# Lab2_Schematic.net
KiCad netlist of a schematic drawn in EAGLE
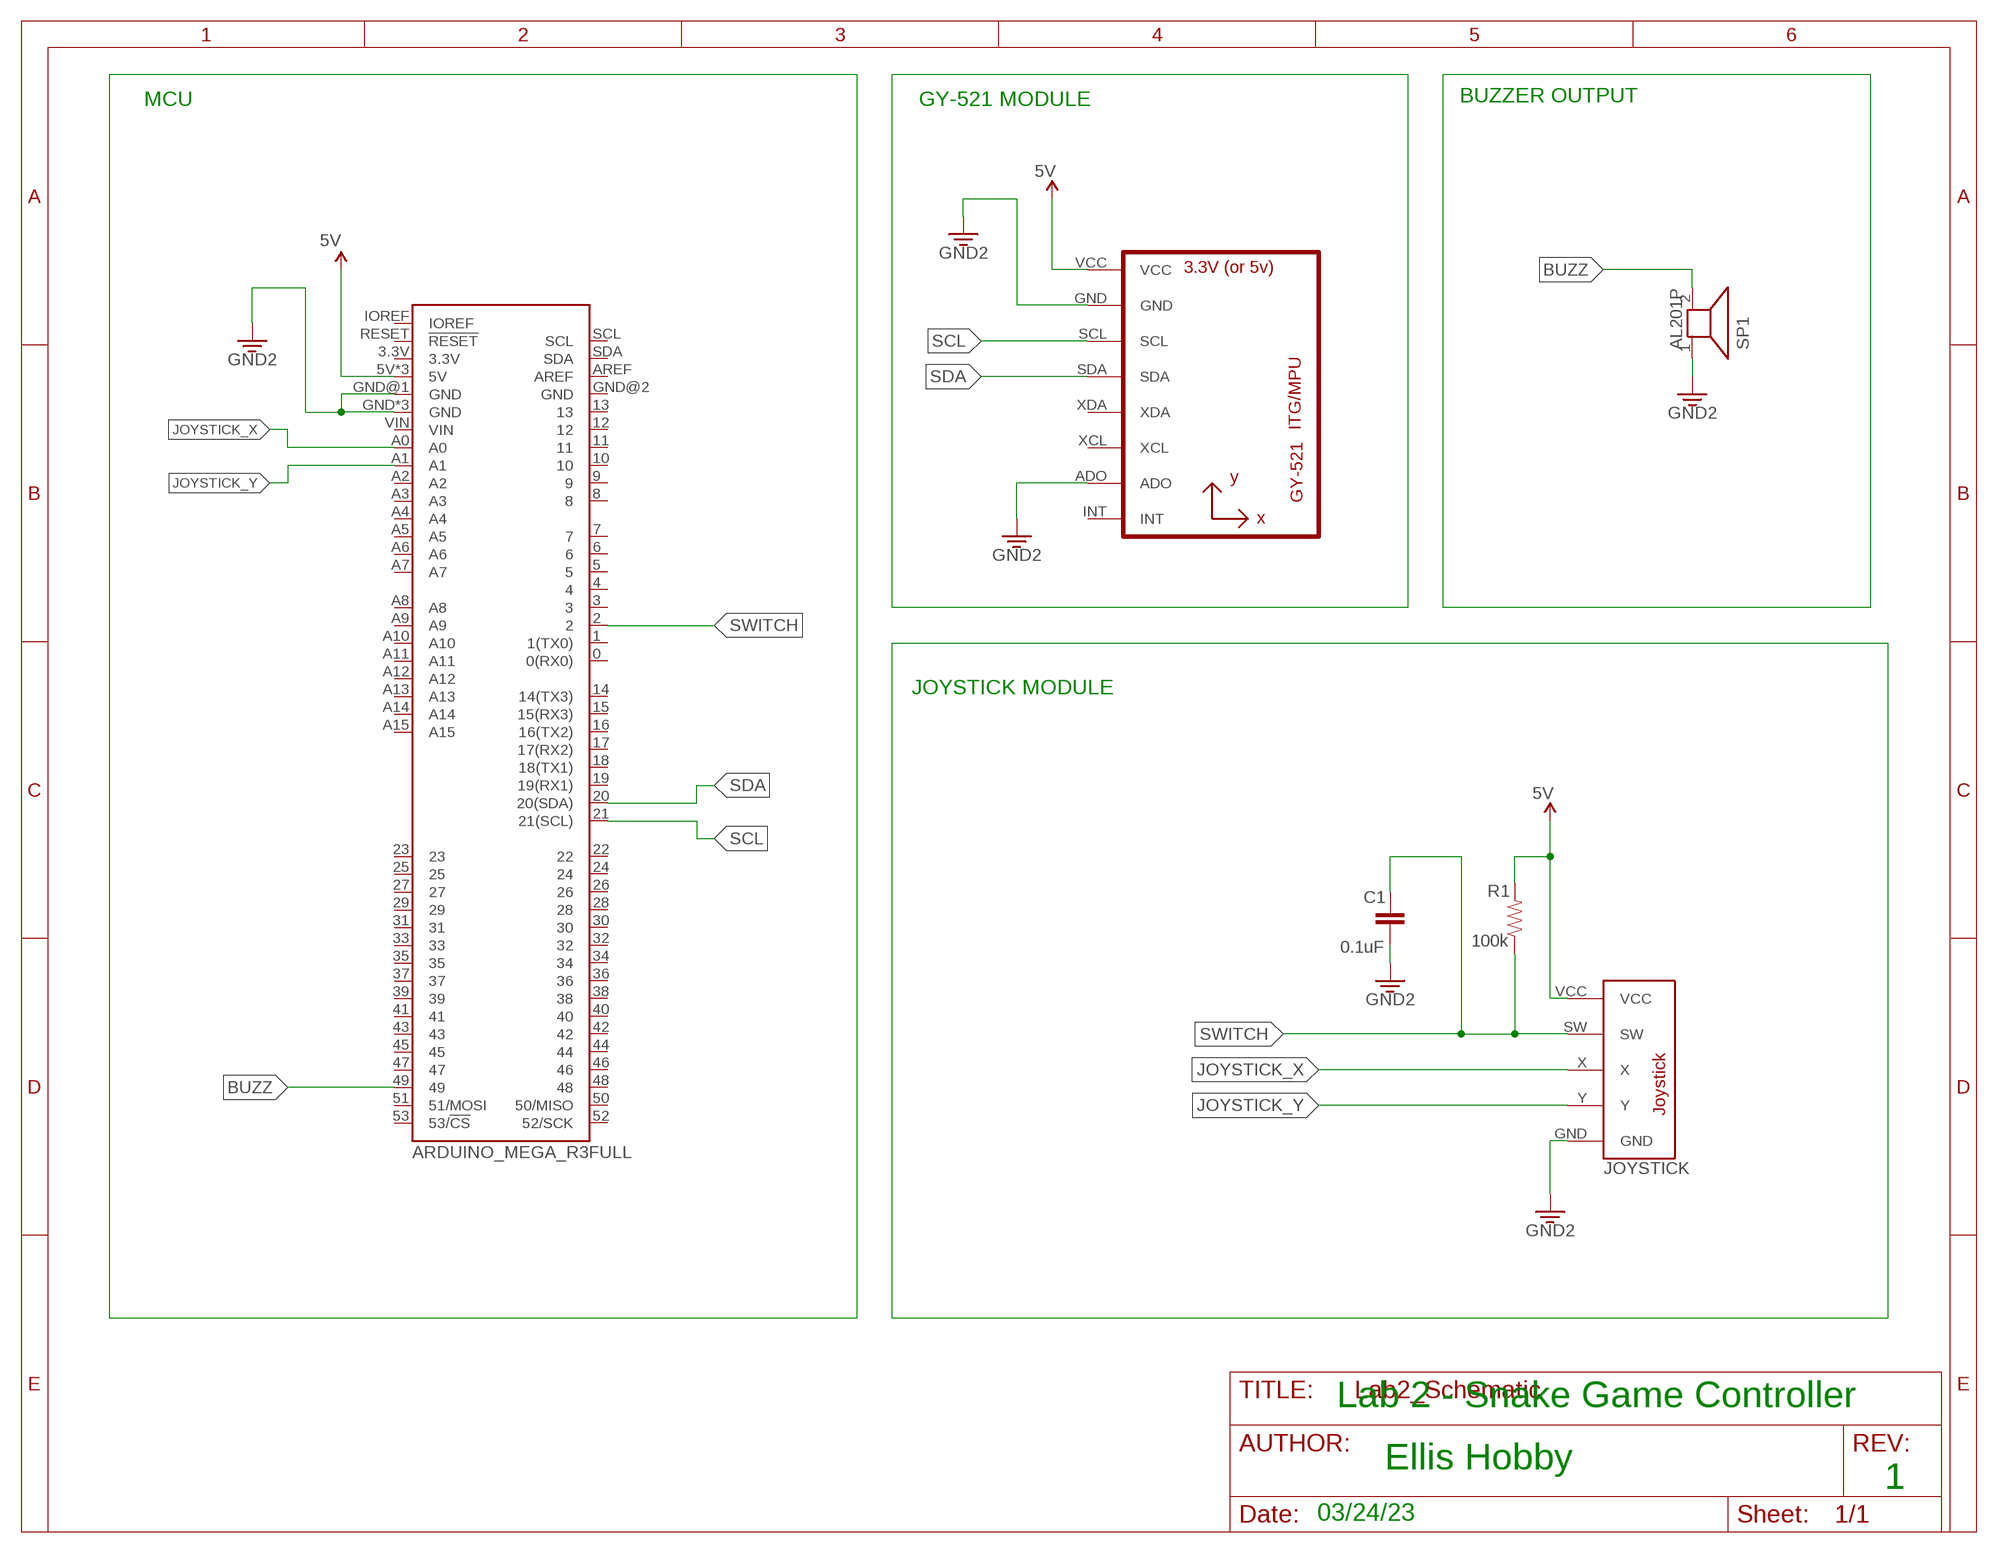
[diagram p0: schematic, sheet 1]

(export (version "E")
  (design (tool "Eeschema 10.0.6"))
  (components
    (comp (ref "B2")
      (value "ARDUINO_MEGA_R3FULL")
      (footprint "eagle-import:ARDUINO_MEGA_NO_SILK")
      (libsource (lib "eagle-import") (part "ARDUINO_MEGA_R3FULL"))
    )
    (comp (ref "C1")
      (value "0.1uF")
      (footprint "eagle-import:CAP-PTH-SMALL-KIT")
      (libsource (lib "eagle-import") (part "0.1UF-KIT-EZ-50V-20%"))
    )
    (comp (ref "R1")
      (value "100k")
      (footprint "eagle-import:AXIAL-0.3")
      (libsource (lib "eagle-import") (part "1KOHM-HORIZ-1/4W-1%"))
    )
    (comp (ref "SP1")
      (value "AL201P")
      (footprint "eagle-import:AL201P")
      (libsource (lib "eagle-import") (part "AL201P"))
    )
    (comp (ref "SW1")
      (value "JOYSTICK")
      (footprint "eagle-import:JOYSTICK-PSP1000")
      (libsource (lib "eagle-import") (part "JOYSTICK_SLIDE"))
    )
    (comp (ref "U1")
      (value "GY-521MPU6050")
      (footprint "eagle-import:GY-521")
      (libsource (lib "eagle-import") (part "GY-521MPU6050"))
    )
  )
  (nets
    (net (code "1") (name "5V") (class "Default")
      (node (ref "B2") (pin "5V") (pinfunction "5V_5V") (pintype "bidirectional"))
      (node (ref "B2") (pin "5V@1") (pinfunction "5V_5V@1") (pintype "bidirectional"))
      (node (ref "B2") (pin "5V@2") (pinfunction "5V_5V@2") (pintype "bidirectional"))
      (node (ref "R1") (pin "P$2") (pinfunction "2_P$2") (pintype "passive"))
      (node (ref "SW1") (pin "VCC") (pinfunction "VCC_VCC") (pintype "bidirectional"))
      (node (ref "U1") (pin "VCC") (pinfunction "VCC_VCC") (pintype "bidirectional"))
    )
    (net (code "2") (name "BUZZ") (class "Default")
      (node (ref "B2") (pin "49") (pinfunction "49_49") (pintype "bidirectional"))
      (node (ref "SP1") (pin "2") (pinfunction "2_2") (pintype "passive"))
    )
    (net (code "3") (name "GND2") (class "Default")
      (node (ref "B2") (pin "GND") (pinfunction "GND_GND") (pintype "bidirectional"))
      (node (ref "B2") (pin "GND@1") (pinfunction "GND_GND@1") (pintype "bidirectional"))
      (node (ref "B2") (pin "GND@3") (pinfunction "GND_GND@3") (pintype "bidirectional"))
      (node (ref "B2") (pin "GND@4") (pinfunction "GND_GND@4") (pintype "bidirectional"))
      (node (ref "C1") (pin "2") (pinfunction "2_2") (pintype "passive"))
      (node (ref "SP1") (pin "1") (pinfunction "1_1") (pintype "passive"))
      (node (ref "SW1") (pin "GND") (pinfunction "GND_GND") (pintype "bidirectional"))
      (node (ref "U1") (pin "ADO") (pinfunction "ADO_ADO") (pintype "bidirectional"))
      (node (ref "U1") (pin "GND") (pinfunction "GND_GND") (pintype "bidirectional"))
    )
    (net (code "4") (name "JOYSTICK_X") (class "Default")
      (node (ref "B2") (pin "A0") (pinfunction "A0_A0") (pintype "bidirectional"))
      (node (ref "SW1") (pin "X") (pinfunction "X_X") (pintype "bidirectional"))
    )
    (net (code "5") (name "JOYSTICK_Y") (class "Default")
      (node (ref "B2") (pin "A1") (pinfunction "A1_A1") (pintype "bidirectional"))
      (node (ref "SW1") (pin "Y") (pinfunction "Y_Y") (pintype "bidirectional"))
    )
    (net (code "6") (name "SCL") (class "Default")
      (node (ref "B2") (pin "21") (pinfunction "21(SCL)_21") (pintype "bidirectional"))
      (node (ref "U1") (pin "SCL") (pinfunction "SCL_SCL") (pintype "bidirectional"))
    )
    (net (code "7") (name "SDA") (class "Default")
      (node (ref "B2") (pin "20") (pinfunction "20(SDA)_20") (pintype "bidirectional"))
      (node (ref "U1") (pin "SDA") (pinfunction "SDA_SDA") (pintype "bidirectional"))
    )
    (net (code "8") (name "SWITCH") (class "Default")
      (node (ref "B2") (pin "2") (pinfunction "2_2") (pintype "bidirectional"))
      (node (ref "C1") (pin "1") (pinfunction "1_1") (pintype "passive"))
      (node (ref "R1") (pin "P$1") (pinfunction "1_P$1") (pintype "passive"))
      (node (ref "SW1") (pin "SW") (pinfunction "SW_SW") (pintype "bidirectional"))
    )
    (net (code "9") (name "unconnected-(B2-0(RX0)-Pad0)") (class "Default")
      (node (ref "B2") (pin "0") (pinfunction "0(RX0)_0") (pintype "bidirectional"))
    )
    (net (code "10") (name "unconnected-(B2-1(TX0)-Pad1)") (class "Default")
      (node (ref "B2") (pin "1") (pinfunction "1(TX0)_1") (pintype "bidirectional"))
    )
    (net (code "11") (name "unconnected-(B2-14(TX3)-Pad14)") (class "Default")
      (node (ref "B2") (pin "14") (pinfunction "14(TX3)_14") (pintype "bidirectional"))
    )
    (net (code "12") (name "unconnected-(B2-15(RX3)-Pad15)") (class "Default")
      (node (ref "B2") (pin "15") (pinfunction "15(RX3)_15") (pintype "bidirectional"))
    )
    (net (code "13") (name "unconnected-(B2-16(TX2)-Pad16)") (class "Default")
      (node (ref "B2") (pin "16") (pinfunction "16(TX2)_16") (pintype "bidirectional"))
    )
    (net (code "14") (name "unconnected-(B2-17(RX2)-Pad17)") (class "Default")
      (node (ref "B2") (pin "17") (pinfunction "17(RX2)_17") (pintype "bidirectional"))
    )
    (net (code "15") (name "unconnected-(B2-18(TX1)-Pad18)") (class "Default")
      (node (ref "B2") (pin "18") (pinfunction "18(TX1)_18") (pintype "bidirectional"))
    )
    (net (code "16") (name "unconnected-(B2-19(RX1)-Pad19)") (class "Default")
      (node (ref "B2") (pin "19") (pinfunction "19(RX1)_19") (pintype "bidirectional"))
    )
    (net (code "17") (name "unconnected-(B2-50{slash}MISO-Pad50)") (class "Default")
      (node (ref "B2") (pin "50") (pinfunction "50/MISO_50") (pintype "bidirectional"))
    )
    (net (code "18") (name "unconnected-(B2-51{slash}MOSI-Pad51)") (class "Default")
      (node (ref "B2") (pin "51") (pinfunction "51/MOSI_51") (pintype "bidirectional"))
    )
    (net (code "19") (name "unconnected-(B2-52{slash}SCK-Pad52)") (class "Default")
      (node (ref "B2") (pin "52") (pinfunction "52/SCK_52") (pintype "bidirectional"))
    )
    (net (code "20") (name "unconnected-(B2-53{slash}~{CS}-Pad53)") (class "Default")
      (node (ref "B2") (pin "53") (pinfunction "53/~{CS}_53") (pintype "bidirectional"))
    )
    (net (code "21") (name "unconnected-(B2-GND-PadGND@2)") (class "Default")
      (node (ref "B2") (pin "GND@2") (pinfunction "GND_GND@2") (pintype "bidirectional"))
    )
    (net (code "22") (name "unconnected-(B2-Pad3)") (class "Default")
      (node (ref "B2") (pin "3") (pinfunction "3_3") (pintype "bidirectional"))
    )
    (net (code "23") (name "unconnected-(B2-Pad3.3V)") (class "Default")
      (node (ref "B2") (pin "3.3V") (pinfunction "3.3V_3.3V") (pintype "bidirectional"))
    )
    (net (code "24") (name "unconnected-(B2-Pad4)") (class "Default")
      (node (ref "B2") (pin "4") (pinfunction "4_4") (pintype "bidirectional"))
    )
    (net (code "25") (name "unconnected-(B2-Pad5)") (class "Default")
      (node (ref "B2") (pin "5") (pinfunction "5_5") (pintype "bidirectional"))
    )
    (net (code "26") (name "unconnected-(B2-Pad6)") (class "Default")
      (node (ref "B2") (pin "6") (pinfunction "6_6") (pintype "bidirectional"))
    )
    (net (code "27") (name "unconnected-(B2-Pad7)") (class "Default")
      (node (ref "B2") (pin "7") (pinfunction "7_7") (pintype "bidirectional"))
    )
    (net (code "28") (name "unconnected-(B2-Pad8)") (class "Default")
      (node (ref "B2") (pin "8") (pinfunction "8_8") (pintype "bidirectional"))
    )
    (net (code "29") (name "unconnected-(B2-Pad9)") (class "Default")
      (node (ref "B2") (pin "9") (pinfunction "9_9") (pintype "bidirectional"))
    )
    (net (code "30") (name "unconnected-(B2-Pad10)") (class "Default")
      (node (ref "B2") (pin "10") (pinfunction "10_10") (pintype "bidirectional"))
    )
    (net (code "31") (name "unconnected-(B2-Pad11)") (class "Default")
      (node (ref "B2") (pin "11") (pinfunction "11_11") (pintype "bidirectional"))
    )
    (net (code "32") (name "unconnected-(B2-Pad12)") (class "Default")
      (node (ref "B2") (pin "12") (pinfunction "12_12") (pintype "bidirectional"))
    )
    (net (code "33") (name "unconnected-(B2-Pad13)") (class "Default")
      (node (ref "B2") (pin "13") (pinfunction "13_13") (pintype "bidirectional"))
    )
    (net (code "34") (name "unconnected-(B2-Pad22)") (class "Default")
      (node (ref "B2") (pin "22") (pinfunction "22_22") (pintype "bidirectional"))
    )
    (net (code "35") (name "unconnected-(B2-Pad23)") (class "Default")
      (node (ref "B2") (pin "23") (pinfunction "23_23") (pintype "bidirectional"))
    )
    (net (code "36") (name "unconnected-(B2-Pad24)") (class "Default")
      (node (ref "B2") (pin "24") (pinfunction "24_24") (pintype "bidirectional"))
    )
    (net (code "37") (name "unconnected-(B2-Pad25)") (class "Default")
      (node (ref "B2") (pin "25") (pinfunction "25_25") (pintype "bidirectional"))
    )
    (net (code "38") (name "unconnected-(B2-Pad26)") (class "Default")
      (node (ref "B2") (pin "26") (pinfunction "26_26") (pintype "bidirectional"))
    )
    (net (code "39") (name "unconnected-(B2-Pad27)") (class "Default")
      (node (ref "B2") (pin "27") (pinfunction "27_27") (pintype "bidirectional"))
    )
    (net (code "40") (name "unconnected-(B2-Pad28)") (class "Default")
      (node (ref "B2") (pin "28") (pinfunction "28_28") (pintype "bidirectional"))
    )
    (net (code "41") (name "unconnected-(B2-Pad29)") (class "Default")
      (node (ref "B2") (pin "29") (pinfunction "29_29") (pintype "bidirectional"))
    )
    (net (code "42") (name "unconnected-(B2-Pad30)") (class "Default")
      (node (ref "B2") (pin "30") (pinfunction "30_30") (pintype "bidirectional"))
    )
    (net (code "43") (name "unconnected-(B2-Pad31)") (class "Default")
      (node (ref "B2") (pin "31") (pinfunction "31_31") (pintype "bidirectional"))
    )
    (net (code "44") (name "unconnected-(B2-Pad32)") (class "Default")
      (node (ref "B2") (pin "32") (pinfunction "32_32") (pintype "bidirectional"))
    )
    (net (code "45") (name "unconnected-(B2-Pad33)") (class "Default")
      (node (ref "B2") (pin "33") (pinfunction "33_33") (pintype "bidirectional"))
    )
    (net (code "46") (name "unconnected-(B2-Pad34)") (class "Default")
      (node (ref "B2") (pin "34") (pinfunction "34_34") (pintype "bidirectional"))
    )
    (net (code "47") (name "unconnected-(B2-Pad35)") (class "Default")
      (node (ref "B2") (pin "35") (pinfunction "35_35") (pintype "bidirectional"))
    )
    (net (code "48") (name "unconnected-(B2-Pad36)") (class "Default")
      (node (ref "B2") (pin "36") (pinfunction "36_36") (pintype "bidirectional"))
    )
    (net (code "49") (name "unconnected-(B2-Pad37)") (class "Default")
      (node (ref "B2") (pin "37") (pinfunction "37_37") (pintype "bidirectional"))
    )
    (net (code "50") (name "unconnected-(B2-Pad38)") (class "Default")
      (node (ref "B2") (pin "38") (pinfunction "38_38") (pintype "bidirectional"))
    )
    (net (code "51") (name "unconnected-(B2-Pad39)") (class "Default")
      (node (ref "B2") (pin "39") (pinfunction "39_39") (pintype "bidirectional"))
    )
    (net (code "52") (name "unconnected-(B2-Pad40)") (class "Default")
      (node (ref "B2") (pin "40") (pinfunction "40_40") (pintype "bidirectional"))
    )
    (net (code "53") (name "unconnected-(B2-Pad41)") (class "Default")
      (node (ref "B2") (pin "41") (pinfunction "41_41") (pintype "bidirectional"))
    )
    (net (code "54") (name "unconnected-(B2-Pad42)") (class "Default")
      (node (ref "B2") (pin "42") (pinfunction "42_42") (pintype "bidirectional"))
    )
    (net (code "55") (name "unconnected-(B2-Pad43)") (class "Default")
      (node (ref "B2") (pin "43") (pinfunction "43_43") (pintype "bidirectional"))
    )
    (net (code "56") (name "unconnected-(B2-Pad44)") (class "Default")
      (node (ref "B2") (pin "44") (pinfunction "44_44") (pintype "bidirectional"))
    )
    (net (code "57") (name "unconnected-(B2-Pad45)") (class "Default")
      (node (ref "B2") (pin "45") (pinfunction "45_45") (pintype "bidirectional"))
    )
    (net (code "58") (name "unconnected-(B2-Pad46)") (class "Default")
      (node (ref "B2") (pin "46") (pinfunction "46_46") (pintype "bidirectional"))
    )
    (net (code "59") (name "unconnected-(B2-Pad47)") (class "Default")
      (node (ref "B2") (pin "47") (pinfunction "47_47") (pintype "bidirectional"))
    )
    (net (code "60") (name "unconnected-(B2-Pad48)") (class "Default")
      (node (ref "B2") (pin "48") (pinfunction "48_48") (pintype "bidirectional"))
    )
    (net (code "61") (name "unconnected-(B2-PadA2)") (class "Default")
      (node (ref "B2") (pin "A2") (pinfunction "A2_A2") (pintype "bidirectional"))
    )
    (net (code "62") (name "unconnected-(B2-PadA3)") (class "Default")
      (node (ref "B2") (pin "A3") (pinfunction "A3_A3") (pintype "bidirectional"))
    )
    (net (code "63") (name "unconnected-(B2-PadA4)") (class "Default")
      (node (ref "B2") (pin "A4") (pinfunction "A4_A4") (pintype "bidirectional"))
    )
    (net (code "64") (name "unconnected-(B2-PadA5)") (class "Default")
      (node (ref "B2") (pin "A5") (pinfunction "A5_A5") (pintype "bidirectional"))
    )
    (net (code "65") (name "unconnected-(B2-PadA6)") (class "Default")
      (node (ref "B2") (pin "A6") (pinfunction "A6_A6") (pintype "bidirectional"))
    )
    (net (code "66") (name "unconnected-(B2-PadA7)") (class "Default")
      (node (ref "B2") (pin "A7") (pinfunction "A7_A7") (pintype "bidirectional"))
    )
    (net (code "67") (name "unconnected-(B2-PadA8)") (class "Default")
      (node (ref "B2") (pin "A8") (pinfunction "A8_A8") (pintype "bidirectional"))
    )
    (net (code "68") (name "unconnected-(B2-PadA9)") (class "Default")
      (node (ref "B2") (pin "A9") (pinfunction "A9_A9") (pintype "bidirectional"))
    )
    (net (code "69") (name "unconnected-(B2-PadA10)") (class "Default")
      (node (ref "B2") (pin "A10") (pinfunction "A10_A10") (pintype "bidirectional"))
    )
    (net (code "70") (name "unconnected-(B2-PadA11)") (class "Default")
      (node (ref "B2") (pin "A11") (pinfunction "A11_A11") (pintype "bidirectional"))
    )
    (net (code "71") (name "unconnected-(B2-PadA12)") (class "Default")
      (node (ref "B2") (pin "A12") (pinfunction "A12_A12") (pintype "bidirectional"))
    )
    (net (code "72") (name "unconnected-(B2-PadA13)") (class "Default")
      (node (ref "B2") (pin "A13") (pinfunction "A13_A13") (pintype "bidirectional"))
    )
    (net (code "73") (name "unconnected-(B2-PadA14)") (class "Default")
      (node (ref "B2") (pin "A14") (pinfunction "A14_A14") (pintype "bidirectional"))
    )
    (net (code "74") (name "unconnected-(B2-PadA15)") (class "Default")
      (node (ref "B2") (pin "A15") (pinfunction "A15_A15") (pintype "bidirectional"))
    )
    (net (code "75") (name "unconnected-(B2-PadAREF)") (class "Default")
      (node (ref "B2") (pin "AREF") (pinfunction "AREF_AREF") (pintype "bidirectional"))
    )
    (net (code "76") (name "unconnected-(B2-PadIOREF)") (class "Default")
      (node (ref "B2") (pin "IOREF") (pinfunction "IOREF_IOREF") (pintype "bidirectional"))
    )
    (net (code "77") (name "unconnected-(B2-PadSCL)") (class "Default")
      (node (ref "B2") (pin "SCL") (pinfunction "SCL_SCL") (pintype "bidirectional"))
    )
    (net (code "78") (name "unconnected-(B2-PadSDA)") (class "Default")
      (node (ref "B2") (pin "SDA") (pinfunction "SDA_SDA") (pintype "bidirectional"))
    )
    (net (code "79") (name "unconnected-(B2-PadVIN)") (class "Default")
      (node (ref "B2") (pin "VIN") (pinfunction "VIN_VIN") (pintype "bidirectional"))
    )
    (net (code "80") (name "unconnected-(B2-~{RESET}-PadRESET)") (class "Default")
      (node (ref "B2") (pin "RESET") (pinfunction "~{RESET}_RESET") (pintype "bidirectional"))
    )
    (net (code "81") (name "unconnected-(U1-PadINT)") (class "Default")
      (node (ref "U1") (pin "INT") (pinfunction "INT_INT") (pintype "bidirectional"))
    )
    (net (code "82") (name "unconnected-(U1-PadXCL)") (class "Default")
      (node (ref "U1") (pin "XCL") (pinfunction "XCL_XCL") (pintype "bidirectional"))
    )
    (net (code "83") (name "unconnected-(U1-PadXDA)") (class "Default")
      (node (ref "U1") (pin "XDA") (pinfunction "XDA_XDA") (pintype "bidirectional"))
    )
  )
)
